# BenchPower.net
KiCad netlist of a schematic drawn in EAGLE
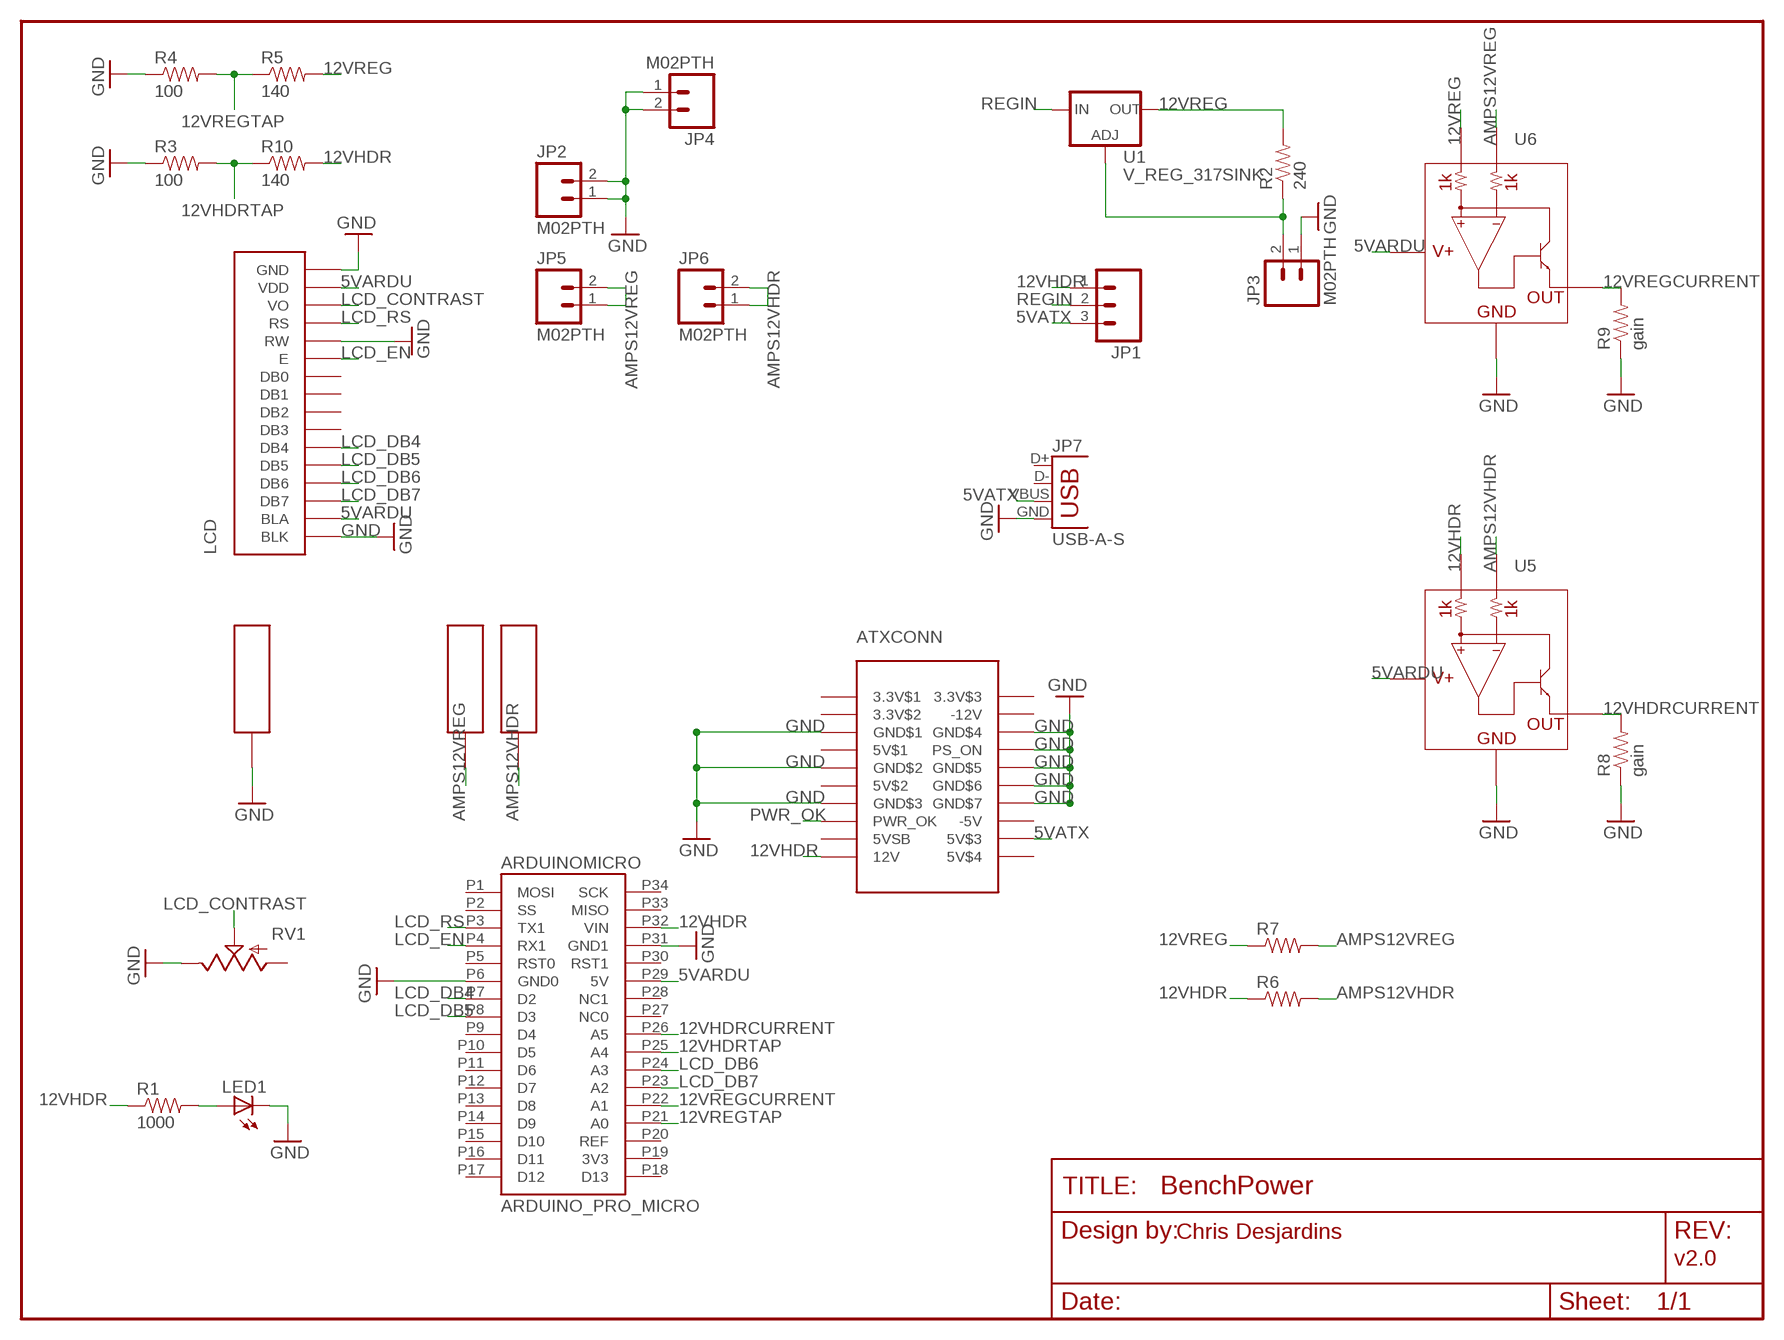
[diagram p0: schematic, sheet 1]

(export (version "E")
  (design (tool "Eeschema 10.0.6"))
  (components
    (comp (ref "ARDUINOMICRO")
      (value "ARDUINO_PRO_MICRO")
      (footprint "eagle-import:ARDUINO_PRO_MICRO")
      (libsource (lib "eagle-import") (part "ARDUINO_PRO_MICRO"))
    )
    (comp (ref "ATXCONN")
      (value "ATXPOWER")
      (footprint "eagle-import:ATXPOWER")
      (libsource (lib "eagle-import") (part "ATXPOWER"))
    )
    (comp (ref "JP1")
      (value "M03PTH")
      (footprint "eagle-import:1X03")
      (libsource (lib "eagle-import") (part "M03PTH"))
    )
    (comp (ref "JP2")
      (value "M02PTH")
      (footprint "eagle-import:1X02")
      (libsource (lib "eagle-import") (part "M02PTH"))
    )
    (comp (ref "JP3")
      (value "M02PTH")
      (footprint "eagle-import:1X02")
      (libsource (lib "eagle-import") (part "M02PTH"))
    )
    (comp (ref "JP4")
      (value "M02PTH")
      (footprint "eagle-import:1X02")
      (libsource (lib "eagle-import") (part "M02PTH"))
    )
    (comp (ref "JP5")
      (value "M02PTH")
      (footprint "eagle-import:1X02")
      (libsource (lib "eagle-import") (part "M02PTH"))
    )
    (comp (ref "JP6")
      (value "M02PTH")
      (footprint "eagle-import:1X02")
      (libsource (lib "eagle-import") (part "M02PTH"))
    )
    (comp (ref "JP7")
      (value "USB-A-S")
      (footprint "eagle-import:USB-A-S")
      (libsource (lib "eagle-import") (part "USB-A-S"))
    )
    (comp (ref "LCD")
      (value "16X2LCDDT162C")
      (footprint "eagle-import:DT162C")
      (libsource (lib "eagle-import") (part "16X2LCDDT162C"))
    )
    (comp (ref "LED1")
      (value "LED3MM")
      (footprint "eagle-import:LED3MM")
      (libsource (lib "eagle-import") (part "LED3MM"))
    )
    (comp (ref "PWR1")
      (value "BINDINGPOST")
      (footprint "eagle-import:BINDINGPOST")
      (libsource (lib "eagle-import") (part "BINDINGPOST"))
    )
    (comp (ref "PWR2")
      (value "BINDINGPOST")
      (footprint "eagle-import:BINDINGPOST")
      (libsource (lib "eagle-import") (part "BINDINGPOST"))
    )
    (comp (ref "R1")
      (value "1000")
      (footprint "eagle-import:AXIAL-0.3")
      (libsource (lib "eagle-import") (part "RESISTORAXIAL-0.3"))
    )
    (comp (ref "R2")
      (value "240")
      (footprint "eagle-import:AXIAL-0.3")
      (libsource (lib "eagle-import") (part "RESISTORAXIAL-0.3"))
    )
    (comp (ref "R3")
      (value "100")
      (footprint "eagle-import:AXIAL-0.3")
      (libsource (lib "eagle-import") (part "RESISTORAXIAL-0.3"))
    )
    (comp (ref "R4")
      (value "100")
      (footprint "eagle-import:AXIAL-0.3")
      (libsource (lib "eagle-import") (part "RESISTORAXIAL-0.3"))
    )
    (comp (ref "R5")
      (value "140")
      (footprint "eagle-import:AXIAL-0.3")
      (libsource (lib "eagle-import") (part "RESISTORAXIAL-0.3"))
    )
    (comp (ref "R6")
      (value "RESISTOR1206")
      (footprint "eagle-import:1206")
      (libsource (lib "eagle-import") (part "SparkFun-Resistors_RESISTOR1206"))
    )
    (comp (ref "R7")
      (value "RESISTOR1206")
      (footprint "eagle-import:1206")
      (libsource (lib "eagle-import") (part "SparkFun-Resistors_RESISTOR1206"))
    )
    (comp (ref "R8")
      (value "gain")
      (footprint "eagle-import:AXIAL-0.3")
      (libsource (lib "eagle-import") (part "RESISTORAXIAL-0.3"))
    )
    (comp (ref "R9")
      (value "gain")
      (footprint "eagle-import:AXIAL-0.3")
      (libsource (lib "eagle-import") (part "RESISTORAXIAL-0.3"))
    )
    (comp (ref "R10")
      (value "140")
      (footprint "eagle-import:AXIAL-0.3")
      (libsource (lib "eagle-import") (part "RESISTORAXIAL-0.3"))
    )
    (comp (ref "RV1")
      (value "POT3266")
      (footprint "eagle-import:3266W")
      (libsource (lib "eagle-import") (part "POT3266"))
    )
    (comp (ref "U$5")
      (value "BINDINGPOST")
      (footprint "eagle-import:BINDINGPOST")
      (libsource (lib "eagle-import") (part "BINDINGPOST"))
    )
    (comp (ref "U1")
      (value "V_REG_317SINK")
      (footprint "eagle-import:TO220-ADJ")
      (libsource (lib "eagle-import") (part "V_REG_317SINK"))
    )
    (comp (ref "U5")
      (value "INA139")
      (footprint "eagle-import:SOT23-5")
      (libsource (lib "eagle-import") (part "INA139"))
    )
    (comp (ref "U6")
      (value "INA139")
      (footprint "eagle-import:SOT23-5")
      (libsource (lib "eagle-import") (part "INA139"))
    )
  )
  (nets
    (net (code "1") (name "/-5V") (class "Default")
      (node (ref "ATXCONN") (pin "P$18") (pinfunction "-5V_P$18") (pintype "power_in"))
    )
    (net (code "2") (name "/-12V") (class "Default")
      (node (ref "ATXCONN") (pin "P$12") (pinfunction "-12V_P$12") (pintype "power_in"))
    )
    (net (code "3") (name "/3.3V$1") (class "Default")
      (node (ref "ATXCONN") (pin "P$1") (pinfunction "3.3V$1_P$1") (pintype "power_in"))
    )
    (net (code "4") (name "/3.3V$2") (class "Default")
      (node (ref "ATXCONN") (pin "P$2") (pinfunction "3.3V$2_P$2") (pintype "power_in"))
    )
    (net (code "5") (name "/3.3V$3") (class "Default")
      (node (ref "ATXCONN") (pin "P$11") (pinfunction "3.3V$3_P$11") (pintype "power_in"))
    )
    (net (code "6") (name "/3V3") (class "Default")
      (node (ref "ARDUINOMICRO") (pin "P19") (pinfunction "3V3_P19") (pintype "power_in"))
    )
    (net (code "7") (name "/5V$1") (class "Default")
      (node (ref "ATXCONN") (pin "P$4") (pinfunction "5V$1_P$4") (pintype "power_in"))
    )
    (net (code "8") (name "/5V$2") (class "Default")
      (node (ref "ATXCONN") (pin "P$6") (pinfunction "5V$2_P$6") (pintype "power_in"))
    )
    (net (code "9") (name "/5V$4") (class "Default")
      (node (ref "ATXCONN") (pin "P$20") (pinfunction "5V$4_P$20") (pintype "power_in"))
    )
    (net (code "10") (name "/5VARDU") (class "Default")
      (node (ref "ARDUINOMICRO") (pin "P29") (pinfunction "5V_P29") (pintype "power_in"))
      (node (ref "LCD") (pin "P$15") (pinfunction "BLA_P$15") (pintype "power_in"))
      (node (ref "LCD") (pin "P$2") (pinfunction "VDD_P$2") (pintype "power_in"))
      (node (ref "U5") (pin "5") (pinfunction "V+_5") (pintype "bidirectional"))
      (node (ref "U6") (pin "5") (pinfunction "V+_5") (pintype "bidirectional"))
    )
    (net (code "11") (name "/5VATX") (class "Default")
      (node (ref "ATXCONN") (pin "P$19") (pinfunction "5V$3_P$19") (pintype "power_in"))
      (node (ref "JP1") (pin "3") (pinfunction "3_3") (pintype "passive"))
      (node (ref "JP7") (pin "VBUS") (pinfunction "VBUS_VBUS") (pintype "bidirectional"))
    )
    (net (code "12") (name "/5VSB") (class "Default")
      (node (ref "ATXCONN") (pin "P$9") (pinfunction "5VSB_P$9") (pintype "power_in"))
    )
    (net (code "13") (name "/12VHDR") (class "Default")
      (node (ref "ARDUINOMICRO") (pin "P32") (pinfunction "VIN_P32") (pintype "power_in"))
      (node (ref "ATXCONN") (pin "P$10") (pinfunction "12V_P$10") (pintype "power_in"))
      (node (ref "JP1") (pin "1") (pinfunction "1_1") (pintype "passive"))
      (node (ref "R1") (pin "P$1") (pinfunction "1_P$1") (pintype "passive"))
      (node (ref "R10") (pin "P$2") (pinfunction "2_P$2") (pintype "passive"))
      (node (ref "R6") (pin "1") (pinfunction "1_1") (pintype "passive"))
      (node (ref "U5") (pin "3") (pinfunction "VIN+_3") (pintype "bidirectional"))
    )
    (net (code "14") (name "/12VHDRCURRENT") (class "Default")
      (node (ref "ARDUINOMICRO") (pin "P26") (pinfunction "A5_P26") (pintype "bidirectional"))
      (node (ref "R8") (pin "P$2") (pinfunction "2_P$2") (pintype "passive"))
      (node (ref "U5") (pin "1") (pinfunction "OUT_1") (pintype "bidirectional"))
    )
    (net (code "15") (name "/12VHDRTAP") (class "Default")
      (node (ref "ARDUINOMICRO") (pin "P25") (pinfunction "A4_P25") (pintype "bidirectional"))
      (node (ref "R10") (pin "P$1") (pinfunction "1_P$1") (pintype "passive"))
      (node (ref "R3") (pin "P$2") (pinfunction "2_P$2") (pintype "passive"))
    )
    (net (code "16") (name "/12VREG") (class "Default")
      (node (ref "R2") (pin "P$2") (pinfunction "2_P$2") (pintype "passive"))
      (node (ref "R5") (pin "P$2") (pinfunction "2_P$2") (pintype "passive"))
      (node (ref "R7") (pin "1") (pinfunction "1_1") (pintype "passive"))
      (node (ref "U1") (pin "OUT") (pinfunction "OUT_OUT") (pintype "output"))
      (node (ref "U6") (pin "3") (pinfunction "VIN+_3") (pintype "bidirectional"))
    )
    (net (code "17") (name "/12VREGCURRENT") (class "Default")
      (node (ref "ARDUINOMICRO") (pin "P22") (pinfunction "A1_P22") (pintype "bidirectional"))
      (node (ref "R9") (pin "P$2") (pinfunction "2_P$2") (pintype "passive"))
      (node (ref "U6") (pin "1") (pinfunction "OUT_1") (pintype "bidirectional"))
    )
    (net (code "18") (name "/12VREGTAP") (class "Default")
      (node (ref "ARDUINOMICRO") (pin "P21") (pinfunction "A0_P21") (pintype "bidirectional"))
      (node (ref "R4") (pin "P$2") (pinfunction "2_P$2") (pintype "passive"))
      (node (ref "R5") (pin "P$1") (pinfunction "1_P$1") (pintype "passive"))
    )
    (net (code "19") (name "/AMPS12VHDR") (class "Default")
      (node (ref "JP6") (pin "1") (pinfunction "1_1") (pintype "passive"))
      (node (ref "JP6") (pin "2") (pinfunction "2_2") (pintype "passive"))
      (node (ref "PWR2") (pin "P$1") (pinfunction "P$1_P$1") (pintype "power_in"))
      (node (ref "R6") (pin "2") (pinfunction "2_2") (pintype "passive"))
      (node (ref "U5") (pin "4") (pinfunction "VIN-_4") (pintype "bidirectional"))
    )
    (net (code "20") (name "/AMPS12VREG") (class "Default")
      (node (ref "JP5") (pin "1") (pinfunction "1_1") (pintype "passive"))
      (node (ref "JP5") (pin "2") (pinfunction "2_2") (pintype "passive"))
      (node (ref "PWR1") (pin "P$1") (pinfunction "P$1_P$1") (pintype "power_in"))
      (node (ref "R7") (pin "2") (pinfunction "2_2") (pintype "passive"))
      (node (ref "U6") (pin "4") (pinfunction "VIN-_4") (pintype "bidirectional"))
    )
    (net (code "21") (name "/LCD_CONTRAST") (class "Default")
      (node (ref "LCD") (pin "P$3") (pinfunction "VO_P$3") (pintype "power_in"))
      (node (ref "RV1") (pin "P$2") (pinfunction "S_P$2") (pintype "passive"))
    )
    (net (code "22") (name "/LCD_DB4") (class "Default")
      (node (ref "ARDUINOMICRO") (pin "P7") (pinfunction "D2_P7") (pintype "bidirectional"))
      (node (ref "LCD") (pin "P$11") (pinfunction "DB4_P$11") (pintype "bidirectional"))
    )
    (net (code "23") (name "/LCD_DB5") (class "Default")
      (node (ref "ARDUINOMICRO") (pin "P8") (pinfunction "D3_P8") (pintype "bidirectional"))
      (node (ref "LCD") (pin "P$12") (pinfunction "DB5_P$12") (pintype "bidirectional"))
    )
    (net (code "24") (name "/LCD_DB6") (class "Default")
      (node (ref "ARDUINOMICRO") (pin "P24") (pinfunction "A3_P24") (pintype "bidirectional"))
      (node (ref "LCD") (pin "P$13") (pinfunction "DB6_P$13") (pintype "bidirectional"))
    )
    (net (code "25") (name "/LCD_DB7") (class "Default")
      (node (ref "ARDUINOMICRO") (pin "P23") (pinfunction "A2_P23") (pintype "bidirectional"))
      (node (ref "LCD") (pin "P$14") (pinfunction "DB7_P$14") (pintype "bidirectional"))
    )
    (net (code "26") (name "/LCD_EN") (class "Default")
      (node (ref "ARDUINOMICRO") (pin "P4") (pinfunction "RX1_P4") (pintype "bidirectional"))
      (node (ref "LCD") (pin "P$6") (pinfunction "E_P$6") (pintype "bidirectional"))
    )
    (net (code "27") (name "/LCD_RS") (class "Default")
      (node (ref "ARDUINOMICRO") (pin "P3") (pinfunction "TX1_P3") (pintype "bidirectional"))
      (node (ref "LCD") (pin "P$4") (pinfunction "RS_P$4") (pintype "bidirectional"))
    )
    (net (code "28") (name "/PWR_OK") (class "Default")
      (node (ref "ATXCONN") (pin "P$8") (pinfunction "PWR_OK_P$8") (pintype "power_in"))
    )
    (net (code "29") (name "/REF") (class "Default")
      (node (ref "ARDUINOMICRO") (pin "P20") (pinfunction "REF_P20") (pintype "power_in"))
    )
    (net (code "30") (name "/REGIN") (class "Default")
      (node (ref "JP1") (pin "2") (pinfunction "2_2") (pintype "passive"))
      (node (ref "U1") (pin "IN") (pinfunction "IN_IN") (pintype "input"))
    )
    (net (code "31") (name "GND") (class "Default")
      (node (ref "ARDUINOMICRO") (pin "P31") (pinfunction "GND1_P31") (pintype "power_in"))
      (node (ref "ARDUINOMICRO") (pin "P6") (pinfunction "GND0_P6") (pintype "power_in"))
      (node (ref "ATXCONN") (pin "P$13") (pinfunction "GND$4_P$13") (pintype "power_in"))
      (node (ref "ATXCONN") (pin "P$14") (pinfunction "PS_ON_P$14") (pintype "power_in"))
      (node (ref "ATXCONN") (pin "P$15") (pinfunction "GND$5_P$15") (pintype "power_in"))
      (node (ref "ATXCONN") (pin "P$16") (pinfunction "GND$6_P$16") (pintype "power_in"))
      (node (ref "ATXCONN") (pin "P$17") (pinfunction "GND$7_P$17") (pintype "power_in"))
      (node (ref "ATXCONN") (pin "P$3") (pinfunction "GND$1_P$3") (pintype "power_in"))
      (node (ref "ATXCONN") (pin "P$5") (pinfunction "GND$2_P$5") (pintype "power_in"))
      (node (ref "ATXCONN") (pin "P$7") (pinfunction "GND$3_P$7") (pintype "power_in"))
      (node (ref "JP2") (pin "1") (pinfunction "1_1") (pintype "passive"))
      (node (ref "JP2") (pin "2") (pinfunction "2_2") (pintype "passive"))
      (node (ref "JP3") (pin "1") (pinfunction "1_1") (pintype "passive"))
      (node (ref "JP4") (pin "1") (pinfunction "1_1") (pintype "passive"))
      (node (ref "JP4") (pin "2") (pinfunction "2_2") (pintype "passive"))
      (node (ref "JP7") (pin "GND") (pinfunction "GND_GND") (pintype "bidirectional"))
      (node (ref "LCD") (pin "P$1") (pinfunction "GND_P$1") (pintype "power_in"))
      (node (ref "LCD") (pin "P$16") (pinfunction "BLK_P$16") (pintype "power_in"))
      (node (ref "LCD") (pin "P$5") (pinfunction "RW_P$5") (pintype "bidirectional"))
      (node (ref "LED1") (pin "K") (pinfunction "C_K") (pintype "passive"))
      (node (ref "R3") (pin "P$1") (pinfunction "1_P$1") (pintype "passive"))
      (node (ref "R4") (pin "P$1") (pinfunction "1_P$1") (pintype "passive"))
      (node (ref "R8") (pin "P$1") (pinfunction "1_P$1") (pintype "passive"))
      (node (ref "R9") (pin "P$1") (pinfunction "1_P$1") (pintype "passive"))
      (node (ref "RV1") (pin "P$1") (pinfunction "E_P$1") (pintype "passive"))
      (node (ref "U$5") (pin "P$1") (pinfunction "P$1_P$1") (pintype "power_in"))
      (node (ref "U5") (pin "2") (pinfunction "GND_2") (pintype "bidirectional"))
      (node (ref "U6") (pin "2") (pinfunction "GND_2") (pintype "bidirectional"))
    )
    (net (code "32") (name "Net-(R1-2)") (class "Default")
      (node (ref "LED1") (pin "A") (pinfunction "A_A") (pintype "passive"))
      (node (ref "R1") (pin "P$2") (pinfunction "2_P$2") (pintype "passive"))
    )
    (net (code "33") (name "Net-(R2-1)") (class "Default")
      (node (ref "JP3") (pin "2") (pinfunction "2_2") (pintype "passive"))
      (node (ref "R2") (pin "P$1") (pinfunction "1_P$1") (pintype "passive"))
      (node (ref "U1") (pin "ADJ") (pinfunction "ADJ_ADJ") (pintype "input"))
    )
    (net (code "34") (name "unconnected-(ARDUINOMICRO-D4-PadP9)") (class "Default")
      (node (ref "ARDUINOMICRO") (pin "P9") (pinfunction "D4_P9") (pintype "bidirectional"))
    )
    (net (code "35") (name "unconnected-(ARDUINOMICRO-D5-PadP10)") (class "Default")
      (node (ref "ARDUINOMICRO") (pin "P10") (pinfunction "D5_P10") (pintype "bidirectional"))
    )
    (net (code "36") (name "unconnected-(ARDUINOMICRO-D6-PadP11)") (class "Default")
      (node (ref "ARDUINOMICRO") (pin "P11") (pinfunction "D6_P11") (pintype "bidirectional"))
    )
    (net (code "37") (name "unconnected-(ARDUINOMICRO-D7-PadP12)") (class "Default")
      (node (ref "ARDUINOMICRO") (pin "P12") (pinfunction "D7_P12") (pintype "bidirectional"))
    )
    (net (code "38") (name "unconnected-(ARDUINOMICRO-D8-PadP13)") (class "Default")
      (node (ref "ARDUINOMICRO") (pin "P13") (pinfunction "D8_P13") (pintype "bidirectional"))
    )
    (net (code "39") (name "unconnected-(ARDUINOMICRO-D9-PadP14)") (class "Default")
      (node (ref "ARDUINOMICRO") (pin "P14") (pinfunction "D9_P14") (pintype "bidirectional"))
    )
    (net (code "40") (name "unconnected-(ARDUINOMICRO-D10-PadP15)") (class "Default")
      (node (ref "ARDUINOMICRO") (pin "P15") (pinfunction "D10_P15") (pintype "bidirectional"))
    )
    (net (code "41") (name "unconnected-(ARDUINOMICRO-D11-PadP16)") (class "Default")
      (node (ref "ARDUINOMICRO") (pin "P16") (pinfunction "D11_P16") (pintype "bidirectional"))
    )
    (net (code "42") (name "unconnected-(ARDUINOMICRO-D12-PadP17)") (class "Default")
      (node (ref "ARDUINOMICRO") (pin "P17") (pinfunction "D12_P17") (pintype "bidirectional"))
    )
    (net (code "43") (name "unconnected-(ARDUINOMICRO-D13-PadP18)") (class "Default")
      (node (ref "ARDUINOMICRO") (pin "P18") (pinfunction "D13_P18") (pintype "bidirectional"))
    )
    (net (code "44") (name "unconnected-(ARDUINOMICRO-MISO-PadP33)") (class "Default")
      (node (ref "ARDUINOMICRO") (pin "P33") (pinfunction "MISO_P33") (pintype "bidirectional"))
    )
    (net (code "45") (name "unconnected-(ARDUINOMICRO-MOSI-PadP1)") (class "Default")
      (node (ref "ARDUINOMICRO") (pin "P1") (pinfunction "MOSI_P1") (pintype "bidirectional"))
    )
    (net (code "46") (name "unconnected-(ARDUINOMICRO-NC0-PadP27)") (class "Default")
      (node (ref "ARDUINOMICRO") (pin "P27") (pinfunction "NC0_P27") (pintype "no_connect"))
    )
    (net (code "47") (name "unconnected-(ARDUINOMICRO-NC1-PadP28)") (class "Default")
      (node (ref "ARDUINOMICRO") (pin "P28") (pinfunction "NC1_P28") (pintype "no_connect"))
    )
    (net (code "48") (name "unconnected-(ARDUINOMICRO-RST0-PadP5)") (class "Default")
      (node (ref "ARDUINOMICRO") (pin "P5") (pinfunction "RST0_P5") (pintype "bidirectional"))
    )
    (net (code "49") (name "unconnected-(ARDUINOMICRO-RST1-PadP30)") (class "Default")
      (node (ref "ARDUINOMICRO") (pin "P30") (pinfunction "RST1_P30") (pintype "bidirectional"))
    )
    (net (code "50") (name "unconnected-(ARDUINOMICRO-SCK-PadP34)") (class "Default")
      (node (ref "ARDUINOMICRO") (pin "P34") (pinfunction "SCK_P34") (pintype "bidirectional"))
    )
    (net (code "51") (name "unconnected-(ARDUINOMICRO-SS-PadP2)") (class "Default")
      (node (ref "ARDUINOMICRO") (pin "P2") (pinfunction "SS_P2") (pintype "bidirectional"))
    )
    (net (code "52") (name "unconnected-(JP7-PadD+)") (class "Default")
      (node (ref "JP7") (pin "D+") (pinfunction "D+_D+") (pintype "bidirectional"))
    )
    (net (code "53") (name "unconnected-(JP7-PadD-)") (class "Default")
      (node (ref "JP7") (pin "D-") (pinfunction "D-_D-") (pintype "bidirectional"))
    )
    (net (code "54") (name "unconnected-(LCD-DB0-PadP$7)") (class "Default")
      (node (ref "LCD") (pin "P$7") (pinfunction "DB0_P$7") (pintype "bidirectional"))
    )
    (net (code "55") (name "unconnected-(LCD-DB1-PadP$8)") (class "Default")
      (node (ref "LCD") (pin "P$8") (pinfunction "DB1_P$8") (pintype "bidirectional"))
    )
    (net (code "56") (name "unconnected-(LCD-DB2-PadP$9)") (class "Default")
      (node (ref "LCD") (pin "P$9") (pinfunction "DB2_P$9") (pintype "bidirectional"))
    )
    (net (code "57") (name "unconnected-(LCD-DB3-PadP$10)") (class "Default")
      (node (ref "LCD") (pin "P$10") (pinfunction "DB3_P$10") (pintype "bidirectional"))
    )
    (net (code "58") (name "unconnected-(RV1-A-PadP$3)") (class "Default")
      (node (ref "RV1") (pin "P$3") (pinfunction "A_P$3") (pintype "passive"))
    )
  )
)
